# ProPrj__stm32_PAW3395__2025-03-07.net
KiCad netlist of a schematic drawn in EasyEDA Pro
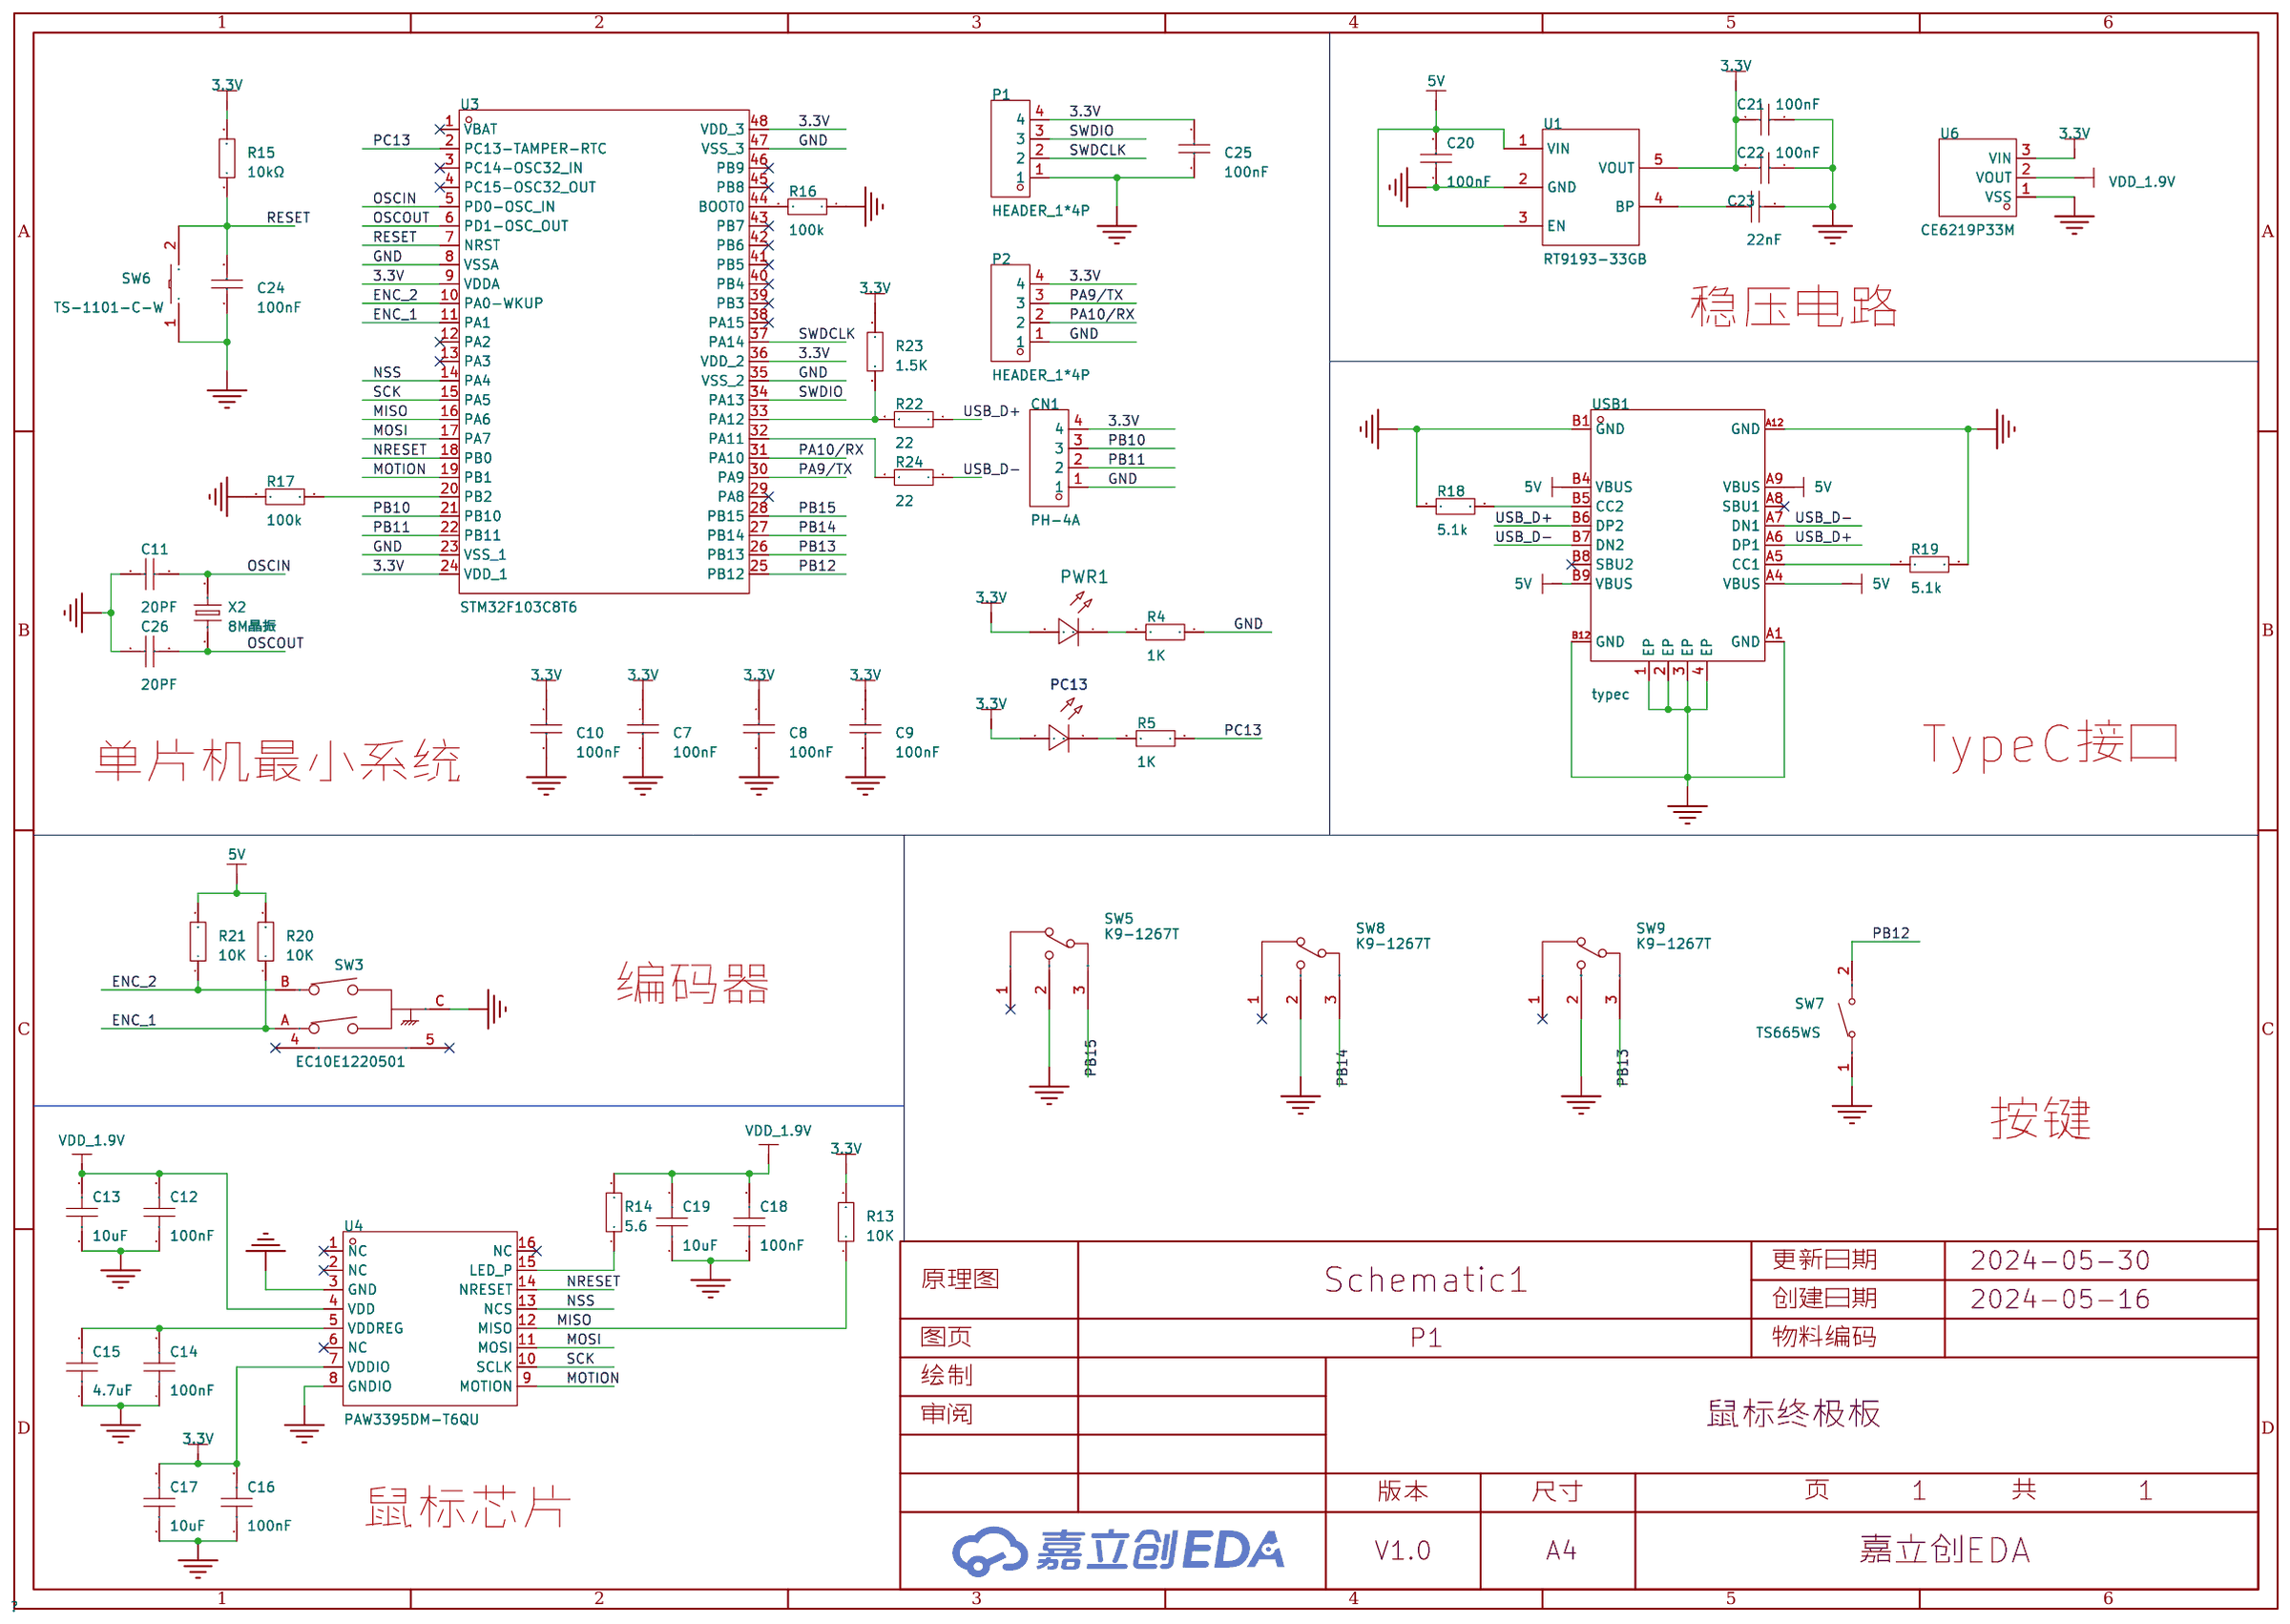
[diagram p0: schematic sheet]

(export (version "E")
  (design (tool "Eeschema 10.0.6"))
  (components
    (comp (ref "C7")
      (value "100nF")
      (footprint "easyedapro:C0603")
      (description "容值:100nF;精度:±10%;额定电压:50V;材质(温度系数):X7R;")
      (fields (field (name "Manufacturer Part") "0603B104K500NT") (field (name "Manufacturer") "FH(风华)"))
      (libsource (lib "easyedapro") (part "0603B104K500NT"))
    )
    (comp (ref "C8")
      (value "100nF")
      (footprint "easyedapro:C0603")
      (description "容值:100nF;精度:±10%;额定电压:50V;材质(温度系数):X7R;")
      (fields (field (name "Manufacturer Part") "0603B104K500NT") (field (name "Manufacturer") "FH(风华)"))
      (libsource (lib "easyedapro") (part "0603B104K500NT"))
    )
    (comp (ref "C9")
      (value "100nF")
      (footprint "easyedapro:C0603")
      (description "容值:100nF;精度:±10%;额定电压:50V;材质(温度系数):X7R;")
      (fields (field (name "Manufacturer Part") "0603B104K500NT") (field (name "Manufacturer") "FH(风华)"))
      (libsource (lib "easyedapro") (part "0603B104K500NT"))
    )
    (comp (ref "C10")
      (value "100nF")
      (footprint "easyedapro:C0603")
      (description "容值:100nF;精度:±10%;额定电压:50V;材质(温度系数):X7R;")
      (fields (field (name "Manufacturer Part") "0603B104K500NT") (field (name "Manufacturer") "FH(风华)"))
      (libsource (lib "easyedapro") (part "0603B104K500NT"))
    )
    (comp (ref "C11")
      (value "20PF")
      (footprint "easyedapro:C0603")
      (description "容值:100nF;精度:±10%;额定电压:50V;材质(温度系数):X7R;")
      (fields (field (name "Manufacturer Part") "0603B104K500NT") (field (name "Manufacturer") "FH(风华)"))
      (libsource (lib "easyedapro") (part "0603B104K500NT"))
    )
    (comp (ref "C12")
      (value "100nF")
      (footprint "easyedapro:C0603")
      (libsource (lib "easyedapro") (part "CapAcitance"))
    )
    (comp (ref "C13")
      (value "10uF")
      (footprint "easyedapro:C0603")
      (libsource (lib "easyedapro") (part "CapAcitance"))
    )
    (comp (ref "C14")
      (value "100nF")
      (footprint "easyedapro:C0603")
      (libsource (lib "easyedapro") (part "CapAcitance"))
    )
    (comp (ref "C15")
      (value "4.7uF")
      (footprint "easyedapro:C0603")
      (libsource (lib "easyedapro") (part "CapAcitance"))
    )
    (comp (ref "C16")
      (value "100nF")
      (footprint "easyedapro:C0603")
      (libsource (lib "easyedapro") (part "CapAcitance"))
    )
    (comp (ref "C17")
      (value "10uF")
      (footprint "easyedapro:C0603")
      (libsource (lib "easyedapro") (part "CapAcitance"))
    )
    (comp (ref "C18")
      (value "100nF")
      (footprint "easyedapro:C0603")
      (libsource (lib "easyedapro") (part "CapAcitance"))
    )
    (comp (ref "C19")
      (value "10uF")
      (footprint "easyedapro:C0603")
      (libsource (lib "easyedapro") (part "CapAcitance"))
    )
    (comp (ref "C20")
      (value "100nF")
      (footprint "easyedapro:C0603")
      (description "容值:100nF;精度:±10%;额定电压:50V;材质(温度系数):X7R;")
      (fields (field (name "Manufacturer Part") "0603B104K500NT") (field (name "Manufacturer") "FH(风华)"))
      (libsource (lib "easyedapro") (part "0603B104K500NT"))
    )
    (comp (ref "C21")
      (value "100nF")
      (footprint "easyedapro:C0603")
      (description "容值:100nF;精度:±10%;额定电压:50V;材质(温度系数):X7R;")
      (fields (field (name "Manufacturer Part") "0603B104K500NT") (field (name "Manufacturer") "FH(风华)"))
      (libsource (lib "easyedapro") (part "0603B104K500NT"))
    )
    (comp (ref "C22")
      (value "100nF")
      (footprint "easyedapro:C0603")
      (description "容值:100nF;精度:±10%;额定电压:50V;材质(温度系数):X7R;")
      (fields (field (name "Manufacturer Part") "0603B104K500NT") (field (name "Manufacturer") "FH(风华)"))
      (libsource (lib "easyedapro") (part "0603B104K500NT"))
    )
    (comp (ref "C23")
      (value "22nF")
      (footprint "easyedapro:C0603")
      (description "容值:100nF;精度:±10%;额定电压:50V;材质(温度系数):X7R;")
      (fields (field (name "Manufacturer Part") "0603B104K500NT") (field (name "Manufacturer") "FH(风华)"))
      (libsource (lib "easyedapro") (part "0603B104K500NT"))
    )
    (comp (ref "C24")
      (value "100nF")
      (footprint "easyedapro:C0603")
      (description "容值:100nF;精度:±10%;额定电压:50V;材质(温度系数):X7R;")
      (fields (field (name "Manufacturer Part") "0603B104K500NT") (field (name "Manufacturer") "FH(风华)"))
      (libsource (lib "easyedapro") (part "0603B104K500NT"))
    )
    (comp (ref "C25")
      (value "100nF")
      (footprint "easyedapro:C0603")
      (description "容值:100nF;精度:±10%;额定电压:50V;材质(温度系数):X7R;")
      (fields (field (name "Manufacturer Part") "0603B104K500NT") (field (name "Manufacturer") "FH(风华)"))
      (libsource (lib "easyedapro") (part "0603B104K500NT"))
    )
    (comp (ref "C26")
      (value "20PF")
      (footprint "easyedapro:C0603")
      (description "容值:100nF;精度:±10%;额定电压:50V;材质(温度系数):X7R;")
      (fields (field (name "Manufacturer Part") "0603B104K500NT") (field (name "Manufacturer") "FH(风华)"))
      (libsource (lib "easyedapro") (part "0603B104K500NT"))
    )
    (comp (ref "CN1")
      (value "PH-4A")
      (footprint "easyedapro:CONN-TH_4P-P2.00_PH-4A_C2908625")
      (fields (field (name "Manufacturer") "HCTL(华灿天禄)"))
      (libsource (lib "easyedapro") (part "PH-4A_C2908625"))
    )
    (comp (ref "P1")
      (value "HEADER_1*4P")
      (footprint "easyedapro:HDR-TH_4P-P2.54-V-M-1")
      (libsource (lib "easyedapro") (part "HEADER_1*4P"))
    )
    (comp (ref "P2")
      (value "HEADER_1*4P")
      (footprint "easyedapro:HDR-TH_4P-P2.54-V-M-1")
      (libsource (lib "easyedapro") (part "HEADER_1*4P"))
    )
    (comp (ref "PC13")
      (value "~")
      (footprint "easyedapro:LED_0603")
      (libsource (lib "easyedapro") (part "LED_B"))
    )
    (comp (ref "PWR1")
      (value "~")
      (footprint "easyedapro:LED_0603")
      (libsource (lib "easyedapro") (part "LED_R"))
    )
    (comp (ref "R4")
      (value "1K")
      (footprint "easyedapro:R0603")
      (description "电阻类型:厚膜电阻;阻值:10kΩ;精度:±1%;功率:100mW;")
      (fields
        (field (name "Manufacturer Part") "0603WAF1002T5E")
        (field (name "Manufacturer") "UNI-ROYAL(厚声)")
      )
      (libsource (lib "easyedapro") (part "0603WAF1002T5E"))
    )
    (comp (ref "R5")
      (value "1K")
      (footprint "easyedapro:R0603")
      (description "电阻类型:厚膜电阻;阻值:10kΩ;精度:±1%;功率:100mW;")
      (fields
        (field (name "Manufacturer Part") "0603WAF1002T5E")
        (field (name "Manufacturer") "UNI-ROYAL(厚声)")
      )
      (libsource (lib "easyedapro") (part "0603WAF1002T5E"))
    )
    (comp (ref "R13") (value "10K") (footprint "easyedapro:R0603") (libsource (lib "easyedapro") (part "电阻")))
    (comp (ref "R14") (value "5.6") (footprint "easyedapro:R0603") (libsource (lib "easyedapro") (part "电阻")))
    (comp (ref "R15")
      (value "10kΩ")
      (footprint "easyedapro:R0603")
      (description "电阻类型:厚膜电阻;阻值:10kΩ;精度:±1%;功率:100mW;")
      (fields
        (field (name "Manufacturer Part") "0603WAF1002T5E")
        (field (name "Manufacturer") "UNI-ROYAL(厚声)")
      )
      (libsource (lib "easyedapro") (part "0603WAF1002T5E"))
    )
    (comp (ref "R16")
      (value "100k")
      (footprint "easyedapro:R0603")
      (description "电阻类型:厚膜电阻;阻值:10kΩ;精度:±1%;功率:100mW;")
      (fields
        (field (name "Manufacturer Part") "0603WAF1002T5E")
        (field (name "Manufacturer") "UNI-ROYAL(厚声)")
      )
      (libsource (lib "easyedapro") (part "0603WAF1002T5E"))
    )
    (comp (ref "R17")
      (value "100k")
      (footprint "easyedapro:R0603")
      (description "电阻类型:厚膜电阻;阻值:10kΩ;精度:±1%;功率:100mW;")
      (fields
        (field (name "Manufacturer Part") "0603WAF1002T5E")
        (field (name "Manufacturer") "UNI-ROYAL(厚声)")
      )
      (libsource (lib "easyedapro") (part "0603WAF1002T5E"))
    )
    (comp (ref "R18")
      (value "5.1k")
      (footprint "easyedapro:R0603")
      (libsource (lib "easyedapro") (part "电阻"))
    )
    (comp (ref "R19")
      (value "5.1k")
      (footprint "easyedapro:R0603")
      (libsource (lib "easyedapro") (part "电阻"))
    )
    (comp (ref "R20") (value "10K") (footprint "easyedapro:R0603") (libsource (lib "easyedapro") (part "电阻")))
    (comp (ref "R21") (value "10K") (footprint "easyedapro:R0603") (libsource (lib "easyedapro") (part "电阻")))
    (comp (ref "R22")
      (value "22")
      (footprint "easyedapro:R0603")
      (description "电阻类型:厚膜电阻;阻值:10kΩ;精度:±1%;功率:100mW;")
      (fields
        (field (name "Manufacturer Part") "0603WAF1002T5E")
        (field (name "Manufacturer") "UNI-ROYAL(厚声)")
      )
      (libsource (lib "easyedapro") (part "0603WAF1002T5E"))
    )
    (comp (ref "R23")
      (value "1.5K")
      (footprint "easyedapro:R0603")
      (description "电阻类型:厚膜电阻;阻值:10kΩ;精度:±1%;功率:100mW;")
      (fields
        (field (name "Manufacturer Part") "0603WAF1002T5E")
        (field (name "Manufacturer") "UNI-ROYAL(厚声)")
      )
      (libsource (lib "easyedapro") (part "0603WAF1002T5E"))
    )
    (comp (ref "R24")
      (value "22")
      (footprint "easyedapro:R0603")
      (description "电阻类型:厚膜电阻;阻值:10kΩ;精度:±1%;功率:100mW;")
      (fields
        (field (name "Manufacturer Part") "0603WAF1002T5E")
        (field (name "Manufacturer") "UNI-ROYAL(厚声)")
      )
      (libsource (lib "easyedapro") (part "0603WAF1002T5E"))
    )
    (comp (ref "SW3")
      (value "EC10E1220501")
      (footprint "easyedapro:SW-TH_EC10EXXXXXXX")
      (description "10型贯通轴型")
      (fields (field (name "Manufacturer") "ALPSALPINE(阿尔卑斯阿尔派)"))
      (libsource (lib "easyedapro") (part "EC10E1220501"))
    )
    (comp (ref "SW5")
      (value "K9-1267T")
      (footprint "easyedapro:SW-TH_K9-1267T")
      (description "类型:微动开关;电路结构:单刀双掷;额定电流(DC):100mA;额定电压(DC):30V;额定电流(AC):-;额定电压(AC):-;机械寿命:300万次;")
      (fields (field (name "Manufacturer") "韩国韩荣"))
      (libsource (lib "easyedapro") (part "K9-1267T"))
    )
    (comp (ref "SW6")
      (value "TS-1101-C-W")
      (footprint "easyedapro:SW-SMD_L6.0-W3.3-LS8.0")
      (description "触点电流:50mA;额定电压(AC):-;额定电压(DC):12V;额定功率:-;绝缘电阻:-;电路结构:单刀单掷;安装方式:立贴;带灯:无;作用力:260gf;机械寿命:5万次;带支架:否;")
      (fields (field (name "Manufacturer") "XKB Connectivity(中国星坤)"))
      (libsource (lib "easyedapro") (part "TS-1101-C-W"))
    )
    (comp (ref "SW7")
      (value "TS665WS")
      (footprint "easyedapro:SW-SMD_L6.0-W6.0-LS6.6")
      (fields (field (name "Manufacturer") "SHOU HAN(首韩)"))
      (libsource (lib "easyedapro") (part "TS665WS"))
    )
    (comp (ref "SW8")
      (value "K9-1267T")
      (footprint "easyedapro:SW-TH_K9-1267T")
      (description "类型:微动开关;电路结构:单刀双掷;额定电流(DC):100mA;额定电压(DC):30V;额定电流(AC):-;额定电压(AC):-;机械寿命:300万次;")
      (fields (field (name "Manufacturer") "韩国韩荣"))
      (libsource (lib "easyedapro") (part "K9-1267T"))
    )
    (comp (ref "SW9")
      (value "K9-1267T")
      (footprint "easyedapro:SW-TH_K9-1267T")
      (description "类型:微动开关;电路结构:单刀双掷;额定电流(DC):100mA;额定电压(DC):30V;额定电流(AC):-;额定电压(AC):-;机械寿命:300万次;")
      (fields (field (name "Manufacturer") "韩国韩荣"))
      (libsource (lib "easyedapro") (part "K9-1267T"))
    )
    (comp (ref "U1")
      (value "RT9193-33GB")
      (footprint "easyedapro:SOT-23-5_L3.0-W1.7-P0.95-LS2.8-BL")
      (description "输出类型:固定;输出极性:正;输出通道数:1;最大输入电压:5.5V;输出电压:3.3V;压差:300mV@(300mA);输出电流:300mA;电源纹波抑制比(PSRR):70dB;")
      (fields (field (name "Manufacturer") "RICHTEK(立锜)"))
      (libsource (lib "easyedapro") (part "RT9193-33GB"))
    )
    (comp (ref "U3")
      (value "STM32F103C8T6")
      (footprint "easyedapro:LQFP-48_L7.0-W7.0-P0.50-LS9.0-BL")
      (fields (field (name "Manufacturer") "ST(意法半导体)"))
      (libsource (lib "easyedapro") (part "STM32F103C8T6"))
    )
    (comp (ref "U4")
      (value "PAW3395DM-T6QU")
      (footprint "easyedapro:DIP-16_PAW3395DM-T6QU")
      (libsource (lib "easyedapro") (part "PAW3395DM-T6QU"))
    )
    (comp (ref "U6")
      (value "CE6219P33M")
      (footprint "easyedapro:SOT-23-3_L2.9-W1.6-P1.90-LS2.8-BR")
      (libsource (lib "easyedapro") (part "CE6219P33M"))
    )
    (comp (ref "USB1")
      (value "typec")
      (footprint "easyedapro:USB-C-SMD_KH-TYPE-C-16P")
      (libsource (lib "easyedapro") (part "TYPEC_C9900016956"))
    )
    (comp (ref "X2")
      (value "8M晶振")
      (footprint "easyedapro:HC-49US_L11.5-W4.5-P4.88")
      (description "频率:-;负载电容:-;")
      (fields
        (field (name "Manufacturer Part") "XIHCELNANF-8MHZ")
        (field (name "Manufacturer") "TAITIEN(泰艺电子)")
      )
      (libsource (lib "easyedapro") (part "XIHCELNANF-8MHZ"))
    )
  )
  (nets
    (net (code "1") (name "/ENC_1") (class "Default")
      (node (ref "R20") (pin "1") (pinfunction "1_1") (pintype "input"))
      (node (ref "SW3") (pin "A") (pinfunction "A_A") (pintype "input"))
      (node (ref "U3") (pin "11") (pinfunction "PA1_11") (pintype "unspecified"))
    )
    (net (code "2") (name "/ENC_2") (class "Default")
      (node (ref "R21") (pin "1") (pinfunction "1_1") (pintype "input"))
      (node (ref "SW3") (pin "B") (pinfunction "B_B") (pintype "input"))
      (node (ref "U3") (pin "10") (pinfunction "PA0-WKUP_10") (pintype "unspecified"))
    )
    (net (code "3") (name "/MISO") (class "Default")
      (node (ref "R13") (pin "1") (pinfunction "1_1") (pintype "input"))
      (node (ref "U3") (pin "16") (pinfunction "PA6_16") (pintype "unspecified"))
      (node (ref "U4") (pin "12") (pinfunction "MISO_12") (pintype "input"))
    )
    (net (code "4") (name "/MOSI") (class "Default")
      (node (ref "U3") (pin "17") (pinfunction "PA7_17") (pintype "unspecified"))
      (node (ref "U4") (pin "11") (pinfunction "MOSI_11") (pintype "input"))
    )
    (net (code "5") (name "/MOTION") (class "Default")
      (node (ref "U3") (pin "19") (pinfunction "PB1_19") (pintype "unspecified"))
      (node (ref "U4") (pin "9") (pinfunction "MOTION_9") (pintype "input"))
    )
    (net (code "6") (name "/NRESET") (class "Default")
      (node (ref "U3") (pin "18") (pinfunction "PB0_18") (pintype "unspecified"))
      (node (ref "U4") (pin "14") (pinfunction "NRESET_14") (pintype "input"))
    )
    (net (code "7") (name "/NSS") (class "Default")
      (node (ref "U3") (pin "14") (pinfunction "PA4_14") (pintype "unspecified"))
      (node (ref "U4") (pin "13") (pinfunction "NCS_13") (pintype "input"))
    )
    (net (code "8") (name "/OSCIN") (class "Default")
      (node (ref "C11") (pin "2") (pinfunction "2_2") (pintype "input"))
      (node (ref "U3") (pin "5") (pinfunction "PD0-OSC_IN_5") (pintype "unspecified"))
      (node (ref "X2") (pin "2") (pinfunction "2_2") (pintype "input"))
    )
    (net (code "9") (name "/OSCOUT") (class "Default")
      (node (ref "C26") (pin "2") (pinfunction "2_2") (pintype "input"))
      (node (ref "U3") (pin "6") (pinfunction "PD1-OSC_OUT_6") (pintype "unspecified"))
      (node (ref "X2") (pin "1") (pinfunction "1_1") (pintype "input"))
    )
    (net (code "10") (name "/PA9{slash}TX") (class "Default")
      (node (ref "P2") (pin "3") (pinfunction "3_3") (pintype "input"))
      (node (ref "U3") (pin "30") (pinfunction "PA9_30") (pintype "unspecified"))
    )
    (net (code "11") (name "/PA10{slash}RX") (class "Default")
      (node (ref "P2") (pin "2") (pinfunction "2_2") (pintype "input"))
      (node (ref "U3") (pin "31") (pinfunction "PA10_31") (pintype "unspecified"))
    )
    (net (code "12") (name "/PB10") (class "Default")
      (node (ref "CN1") (pin "3") (pinfunction "3_3") (pintype "unspecified"))
      (node (ref "U3") (pin "21") (pinfunction "PB10_21") (pintype "unspecified"))
    )
    (net (code "13") (name "/PB11") (class "Default")
      (node (ref "CN1") (pin "2") (pinfunction "2_2") (pintype "unspecified"))
      (node (ref "U3") (pin "22") (pinfunction "PB11_22") (pintype "unspecified"))
    )
    (net (code "14") (name "/PB12") (class "Default")
      (node (ref "SW7") (pin "2") (pinfunction "B_2") (pintype "unspecified"))
      (node (ref "U3") (pin "25") (pinfunction "PB12_25") (pintype "unspecified"))
    )
    (net (code "15") (name "/PB13") (class "Default")
      (node (ref "SW9") (pin "3") (pinfunction "NC_3") (pintype "unspecified"))
      (node (ref "U3") (pin "26") (pinfunction "PB13_26") (pintype "unspecified"))
    )
    (net (code "16") (name "/PB14") (class "Default")
      (node (ref "SW8") (pin "3") (pinfunction "NC_3") (pintype "unspecified"))
      (node (ref "U3") (pin "27") (pinfunction "PB14_27") (pintype "unspecified"))
    )
    (net (code "17") (name "/PB15") (class "Default")
      (node (ref "SW5") (pin "3") (pinfunction "NC_3") (pintype "unspecified"))
      (node (ref "U3") (pin "28") (pinfunction "PB15_28") (pintype "unspecified"))
    )
    (net (code "18") (name "/PC13") (class "Default")
      (node (ref "R5") (pin "1") (pinfunction "1_1") (pintype "input"))
      (node (ref "U3") (pin "2") (pinfunction "PC13-TAMPER-RTC_2") (pintype "unspecified"))
    )
    (net (code "19") (name "/RESET") (class "Default")
      (node (ref "C24") (pin "2") (pinfunction "2_2") (pintype "input"))
      (node (ref "R15") (pin "1") (pinfunction "1_1") (pintype "input"))
      (node (ref "SW6") (pin "2") (pinfunction "2_2") (pintype "input"))
      (node (ref "U3") (pin "7") (pinfunction "NRST_7") (pintype "unspecified"))
    )
    (net (code "20") (name "/SCK") (class "Default")
      (node (ref "U3") (pin "15") (pinfunction "PA5_15") (pintype "unspecified"))
      (node (ref "U4") (pin "10") (pinfunction "SCLK_10") (pintype "input"))
    )
    (net (code "21") (name "/SWDCLK") (class "Default")
      (node (ref "P1") (pin "2") (pinfunction "2_2") (pintype "input"))
      (node (ref "U3") (pin "37") (pinfunction "PA14_37") (pintype "unspecified"))
    )
    (net (code "22") (name "/SWDIO") (class "Default")
      (node (ref "P1") (pin "3") (pinfunction "3_3") (pintype "input"))
      (node (ref "U3") (pin "34") (pinfunction "PA13_34") (pintype "unspecified"))
    )
    (net (code "23") (name "/USB_D+") (class "Default")
      (node (ref "R22") (pin "1") (pinfunction "1_1") (pintype "input"))
      (node (ref "USB1") (pin "A6") (pinfunction "DP1_A6") (pintype "unspecified"))
      (node (ref "USB1") (pin "B6") (pinfunction "DP2_B6") (pintype "unspecified"))
    )
    (net (code "24") (name "/USB_D-") (class "Default")
      (node (ref "R24") (pin "1") (pinfunction "1_1") (pintype "input"))
      (node (ref "USB1") (pin "A7") (pinfunction "DN1_A7") (pintype "unspecified"))
      (node (ref "USB1") (pin "B7") (pinfunction "DN2_B7") (pintype "unspecified"))
    )
    (net (code "25") (name "3.3V") (class "Default")
      (node (ref "C10") (pin "1") (pinfunction "1_1") (pintype "input"))
      (node (ref "C16") (pin "2") (pinfunction "2_2") (pintype "input"))
      (node (ref "C17") (pin "2") (pinfunction "2_2") (pintype "input"))
      (node (ref "C21") (pin "2") (pinfunction "2_2") (pintype "input"))
      (node (ref "C22") (pin "2") (pinfunction "2_2") (pintype "input"))
      (node (ref "C25") (pin "1") (pinfunction "1_1") (pintype "input"))
      (node (ref "C7") (pin "1") (pinfunction "1_1") (pintype "input"))
      (node (ref "C8") (pin "1") (pinfunction "1_1") (pintype "input"))
      (node (ref "C9") (pin "1") (pinfunction "1_1") (pintype "input"))
      (node (ref "CN1") (pin "4") (pinfunction "4_4") (pintype "unspecified"))
      (node (ref "P1") (pin "4") (pinfunction "4_4") (pintype "input"))
      (node (ref "P2") (pin "4") (pinfunction "4_4") (pintype "input"))
      (node (ref "PC13") (pin "2") (pinfunction "A_2") (pintype "input"))
      (node (ref "PWR1") (pin "2") (pinfunction "A_2") (pintype "input"))
      (node (ref "R13") (pin "2") (pinfunction "2_2") (pintype "input"))
      (node (ref "R15") (pin "2") (pinfunction "2_2") (pintype "input"))
      (node (ref "R23") (pin "1") (pinfunction "1_1") (pintype "input"))
      (node (ref "U1") (pin "5") (pinfunction "VOUT_5") (pintype "input"))
      (node (ref "U3") (pin "24") (pinfunction "VDD_1_24") (pintype "unspecified"))
      (node (ref "U3") (pin "36") (pinfunction "VDD_2_36") (pintype "unspecified"))
      (node (ref "U3") (pin "48") (pinfunction "VDD_3_48") (pintype "unspecified"))
      (node (ref "U3") (pin "9") (pinfunction "VDDA_9") (pintype "unspecified"))
      (node (ref "U4") (pin "7") (pinfunction "VDDIO_7") (pintype "input"))
      (node (ref "U6") (pin "3") (pinfunction "VIN_3") (pintype "input"))
    )
    (net (code "26") (name "5V") (class "Default")
      (node (ref "C20") (pin "2") (pinfunction "2_2") (pintype "input"))
      (node (ref "R20") (pin "2") (pinfunction "2_2") (pintype "input"))
      (node (ref "R21") (pin "2") (pinfunction "2_2") (pintype "input"))
      (node (ref "U1") (pin "1") (pinfunction "VIN_1") (pintype "input"))
      (node (ref "U1") (pin "3") (pinfunction "EN_3") (pintype "input"))
      (node (ref "USB1") (pin "A4") (pinfunction "VBUS_A4") (pintype "unspecified"))
      (node (ref "USB1") (pin "A9") (pinfunction "VBUS_A9") (pintype "unspecified"))
      (node (ref "USB1") (pin "B4") (pinfunction "VBUS_B4") (pintype "unspecified"))
      (node (ref "USB1") (pin "B9") (pinfunction "VBUS_B9") (pintype "unspecified"))
    )
    (net (code "27") (name "GND") (class "Default")
      (node (ref "C10") (pin "2") (pinfunction "2_2") (pintype "input"))
      (node (ref "C11") (pin "1") (pinfunction "1_1") (pintype "input"))
      (node (ref "C12") (pin "1") (pinfunction "1_1") (pintype "input"))
      (node (ref "C13") (pin "1") (pinfunction "1_1") (pintype "input"))
      (node (ref "C14") (pin "1") (pinfunction "1_1") (pintype "input"))
      (node (ref "C15") (pin "1") (pinfunction "1_1") (pintype "input"))
      (node (ref "C16") (pin "1") (pinfunction "1_1") (pintype "input"))
      (node (ref "C17") (pin "1") (pinfunction "1_1") (pintype "input"))
      (node (ref "C18") (pin "1") (pinfunction "1_1") (pintype "input"))
      (node (ref "C19") (pin "1") (pinfunction "1_1") (pintype "input"))
      (node (ref "C20") (pin "1") (pinfunction "1_1") (pintype "input"))
      (node (ref "C21") (pin "1") (pinfunction "1_1") (pintype "input"))
      (node (ref "C22") (pin "1") (pinfunction "1_1") (pintype "input"))
      (node (ref "C23") (pin "1") (pinfunction "1_1") (pintype "input"))
      (node (ref "C24") (pin "1") (pinfunction "1_1") (pintype "input"))
      (node (ref "C25") (pin "2") (pinfunction "2_2") (pintype "input"))
      (node (ref "C26") (pin "1") (pinfunction "1_1") (pintype "input"))
      (node (ref "C7") (pin "2") (pinfunction "2_2") (pintype "input"))
      (node (ref "C8") (pin "2") (pinfunction "2_2") (pintype "input"))
      (node (ref "C9") (pin "2") (pinfunction "2_2") (pintype "input"))
      (node (ref "CN1") (pin "1") (pinfunction "1_1") (pintype "unspecified"))
      (node (ref "P1") (pin "1") (pinfunction "1_1") (pintype "input"))
      (node (ref "P2") (pin "1") (pinfunction "1_1") (pintype "input"))
      (node (ref "R16") (pin "1") (pinfunction "1_1") (pintype "input"))
      (node (ref "R17") (pin "1") (pinfunction "1_1") (pintype "input"))
      (node (ref "R18") (pin "1") (pinfunction "1_1") (pintype "input"))
      (node (ref "R19") (pin "2") (pinfunction "2_2") (pintype "input"))
      (node (ref "R4") (pin "1") (pinfunction "1_1") (pintype "input"))
      (node (ref "SW3") (pin "C") (pinfunction "C_C") (pintype "input"))
      (node (ref "SW5") (pin "2") (pinfunction "ON_2") (pintype "unspecified"))
      (node (ref "SW6") (pin "1") (pinfunction "1_1") (pintype "input"))
      (node (ref "SW7") (pin "1") (pinfunction "A_1") (pintype "unspecified"))
      (node (ref "SW8") (pin "2") (pinfunction "ON_2") (pintype "unspecified"))
      (node (ref "SW9") (pin "2") (pinfunction "ON_2") (pintype "unspecified"))
      (node (ref "U1") (pin "2") (pinfunction "GND_2") (pintype "input"))
      (node (ref "U3") (pin "23") (pinfunction "VSS_1_23") (pintype "unspecified"))
      (node (ref "U3") (pin "35") (pinfunction "VSS_2_35") (pintype "unspecified"))
      (node (ref "U3") (pin "47") (pinfunction "VSS_3_47") (pintype "unspecified"))
      (node (ref "U3") (pin "8") (pinfunction "VSSA_8") (pintype "unspecified"))
      (node (ref "U4") (pin "3") (pinfunction "GND_3") (pintype "input"))
      (node (ref "U4") (pin "8") (pinfunction "GNDIO_8") (pintype "input"))
      (node (ref "U6") (pin "1") (pinfunction "VSS_1") (pintype "input"))
      (node (ref "USB1") (pin "1") (pinfunction "EP_1") (pintype "unspecified"))
      (node (ref "USB1") (pin "2") (pinfunction "EP_2") (pintype "unspecified"))
      (node (ref "USB1") (pin "3") (pinfunction "EP_3") (pintype "unspecified"))
      (node (ref "USB1") (pin "4") (pinfunction "EP_4") (pintype "unspecified"))
      (node (ref "USB1") (pin "A1") (pinfunction "GND_A1") (pintype "unspecified"))
      (node (ref "USB1") (pin "A12") (pinfunction "GND_A12") (pintype "unspecified"))
      (node (ref "USB1") (pin "B1") (pinfunction "GND_B1") (pintype "unspecified"))
      (node (ref "USB1") (pin "B12") (pinfunction "GND_B12") (pintype "unspecified"))
    )
    (net (code "28") (name "Net-(PC13-C)") (class "Default")
      (node (ref "PC13") (pin "1") (pinfunction "C_1") (pintype "input"))
      (node (ref "R5") (pin "2") (pinfunction "2_2") (pintype "input"))
    )
    (net (code "29") (name "Net-(PWR1-C)") (class "Default")
      (node (ref "PWR1") (pin "1") (pinfunction "C_1") (pintype "input"))
      (node (ref "R4") (pin "2") (pinfunction "2_2") (pintype "input"))
    )
    (net (code "30") (name "Net-(U1-BP)") (class "Default")
      (node (ref "C23") (pin "2") (pinfunction "2_2") (pintype "input"))
      (node (ref "U1") (pin "4") (pinfunction "BP_4") (pintype "input"))
    )
    (net (code "31") (name "Net-(U3-BOOT0)") (class "Default")
      (node (ref "R16") (pin "2") (pinfunction "2_2") (pintype "input"))
      (node (ref "U3") (pin "44") (pinfunction "BOOT0_44") (pintype "unspecified"))
    )
    (net (code "32") (name "Net-(U3-PA11)") (class "Default")
      (node (ref "R24") (pin "2") (pinfunction "2_2") (pintype "input"))
      (node (ref "U3") (pin "32") (pinfunction "PA11_32") (pintype "unspecified"))
    )
    (net (code "33") (name "Net-(U3-PA12)") (class "Default")
      (node (ref "R22") (pin "2") (pinfunction "2_2") (pintype "input"))
      (node (ref "R23") (pin "2") (pinfunction "2_2") (pintype "input"))
      (node (ref "U3") (pin "33") (pinfunction "PA12_33") (pintype "unspecified"))
    )
    (net (code "34") (name "Net-(U3-PB2)") (class "Default")
      (node (ref "R17") (pin "2") (pinfunction "2_2") (pintype "input"))
      (node (ref "U3") (pin "20") (pinfunction "PB2_20") (pintype "unspecified"))
    )
    (net (code "35") (name "Net-(U4-LED_P)") (class "Default")
      (node (ref "R14") (pin "1") (pinfunction "1_1") (pintype "input"))
      (node (ref "U4") (pin "15") (pinfunction "LED_P_15") (pintype "input"))
    )
    (net (code "36") (name "Net-(U4-VDDREG)") (class "Default")
      (node (ref "C14") (pin "2") (pinfunction "2_2") (pintype "input"))
      (node (ref "C15") (pin "2") (pinfunction "2_2") (pintype "input"))
      (node (ref "U4") (pin "5") (pinfunction "VDDREG_5") (pintype "input"))
    )
    (net (code "37") (name "Net-(USB1-CC1)") (class "Default")
      (node (ref "R19") (pin "1") (pinfunction "1_1") (pintype "input"))
      (node (ref "USB1") (pin "A5") (pinfunction "CC1_A5") (pintype "unspecified"))
    )
    (net (code "38") (name "Net-(USB1-CC2)") (class "Default")
      (node (ref "R18") (pin "2") (pinfunction "2_2") (pintype "input"))
      (node (ref "USB1") (pin "B5") (pinfunction "CC2_B5") (pintype "unspecified"))
    )
    (net (code "39") (name "VDD_1.9V") (class "Default")
      (node (ref "C12") (pin "2") (pinfunction "2_2") (pintype "input"))
      (node (ref "C13") (pin "2") (pinfunction "2_2") (pintype "input"))
      (node (ref "C18") (pin "2") (pinfunction "2_2") (pintype "input"))
      (node (ref "C19") (pin "2") (pinfunction "2_2") (pintype "input"))
      (node (ref "R14") (pin "2") (pinfunction "2_2") (pintype "input"))
      (node (ref "U4") (pin "4") (pinfunction "VDD_4") (pintype "input"))
      (node (ref "U6") (pin "2") (pinfunction "VOUT_2") (pintype "input"))
    )
    (net (code "40") (name "unconnected-(SW3-Pad4)") (class "Default")
      (node (ref "SW3") (pin "4") (pinfunction "4_4") (pintype "input+no_connect"))
    )
    (net (code "41") (name "unconnected-(SW3-Pad5)") (class "Default")
      (node (ref "SW3") (pin "5") (pinfunction "5_5") (pintype "input+no_connect"))
    )
    (net (code "42") (name "unconnected-(SW5-C-Pad1)") (class "Default")
      (node (ref "SW5") (pin "1") (pinfunction "C_1") (pintype "unspecified+no_connect"))
    )
    (net (code "43") (name "unconnected-(SW8-C-Pad1)") (class "Default")
      (node (ref "SW8") (pin "1") (pinfunction "C_1") (pintype "unspecified+no_connect"))
    )
    (net (code "44") (name "unconnected-(SW9-C-Pad1)") (class "Default")
      (node (ref "SW9") (pin "1") (pinfunction "C_1") (pintype "unspecified+no_connect"))
    )
    (net (code "45") (name "unconnected-(U3-PA2-Pad12)") (class "Default")
      (node (ref "U3") (pin "12") (pinfunction "PA2_12") (pintype "unspecified+no_connect"))
    )
    (net (code "46") (name "unconnected-(U3-PA3-Pad13)") (class "Default")
      (node (ref "U3") (pin "13") (pinfunction "PA3_13") (pintype "unspecified+no_connect"))
    )
    (net (code "47") (name "unconnected-(U3-PA8-Pad29)") (class "Default")
      (node (ref "U3") (pin "29") (pinfunction "PA8_29") (pintype "unspecified+no_connect"))
    )
    (net (code "48") (name "unconnected-(U3-PA15-Pad38)") (class "Default")
      (node (ref "U3") (pin "38") (pinfunction "PA15_38") (pintype "unspecified+no_connect"))
    )
    (net (code "49") (name "unconnected-(U3-PB3-Pad39)") (class "Default")
      (node (ref "U3") (pin "39") (pinfunction "PB3_39") (pintype "unspecified+no_connect"))
    )
    (net (code "50") (name "unconnected-(U3-PB4-Pad40)") (class "Default")
      (node (ref "U3") (pin "40") (pinfunction "PB4_40") (pintype "unspecified+no_connect"))
    )
    (net (code "51") (name "unconnected-(U3-PB5-Pad41)") (class "Default")
      (node (ref "U3") (pin "41") (pinfunction "PB5_41") (pintype "unspecified+no_connect"))
    )
    (net (code "52") (name "unconnected-(U3-PB6-Pad42)") (class "Default")
      (node (ref "U3") (pin "42") (pinfunction "PB6_42") (pintype "unspecified+no_connect"))
    )
    (net (code "53") (name "unconnected-(U3-PB7-Pad43)") (class "Default")
      (node (ref "U3") (pin "43") (pinfunction "PB7_43") (pintype "unspecified+no_connect"))
    )
    (net (code "54") (name "unconnected-(U3-PB8-Pad45)") (class "Default")
      (node (ref "U3") (pin "45") (pinfunction "PB8_45") (pintype "unspecified+no_connect"))
    )
    (net (code "55") (name "unconnected-(U3-PB9-Pad46)") (class "Default")
      (node (ref "U3") (pin "46") (pinfunction "PB9_46") (pintype "unspecified+no_connect"))
    )
    (net (code "56") (name "unconnected-(U3-PC14-OSC32_IN-Pad3)") (class "Default")
      (node (ref "U3") (pin "3") (pinfunction "PC14-OSC32_IN_3") (pintype "unspecified+no_connect"))
    )
    (net (code "57") (name "unconnected-(U3-PC15-OSC32_OUT-Pad4)") (class "Default")
      (node (ref "U3") (pin "4") (pinfunction "PC15-OSC32_OUT_4") (pintype "unspecified+no_connect"))
    )
    (net (code "58") (name "unconnected-(U3-VBAT-Pad1)") (class "Default")
      (node (ref "U3") (pin "1") (pinfunction "VBAT_1") (pintype "unspecified+no_connect"))
    )
    (net (code "59") (name "unconnected-(U4-NC-Pad1)") (class "Default")
      (node (ref "U4") (pin "1") (pinfunction "NC_1") (pintype "input+no_connect"))
    )
    (net (code "60") (name "unconnected-(U4-NC-Pad2)") (class "Default")
      (node (ref "U4") (pin "2") (pinfunction "NC_2") (pintype "input+no_connect"))
    )
    (net (code "61") (name "unconnected-(U4-NC-Pad6)") (class "Default")
      (node (ref "U4") (pin "6") (pinfunction "NC_6") (pintype "input+no_connect"))
    )
    (net (code "62") (name "unconnected-(U4-NC-Pad16)") (class "Default")
      (node (ref "U4") (pin "16") (pinfunction "NC_16") (pintype "input+no_connect"))
    )
    (net (code "63") (name "unconnected-(USB1-SBU1-PadA8)") (class "Default")
      (node (ref "USB1") (pin "A8") (pinfunction "SBU1_A8") (pintype "unspecified+no_connect"))
    )
    (net (code "64") (name "unconnected-(USB1-SBU2-PadB8)") (class "Default")
      (node (ref "USB1") (pin "B8") (pinfunction "SBU2_B8") (pintype "unspecified+no_connect"))
    )
  )
)
